# interface_temperature.net
KiCad netlist of a schematic drawn in Altium Designer
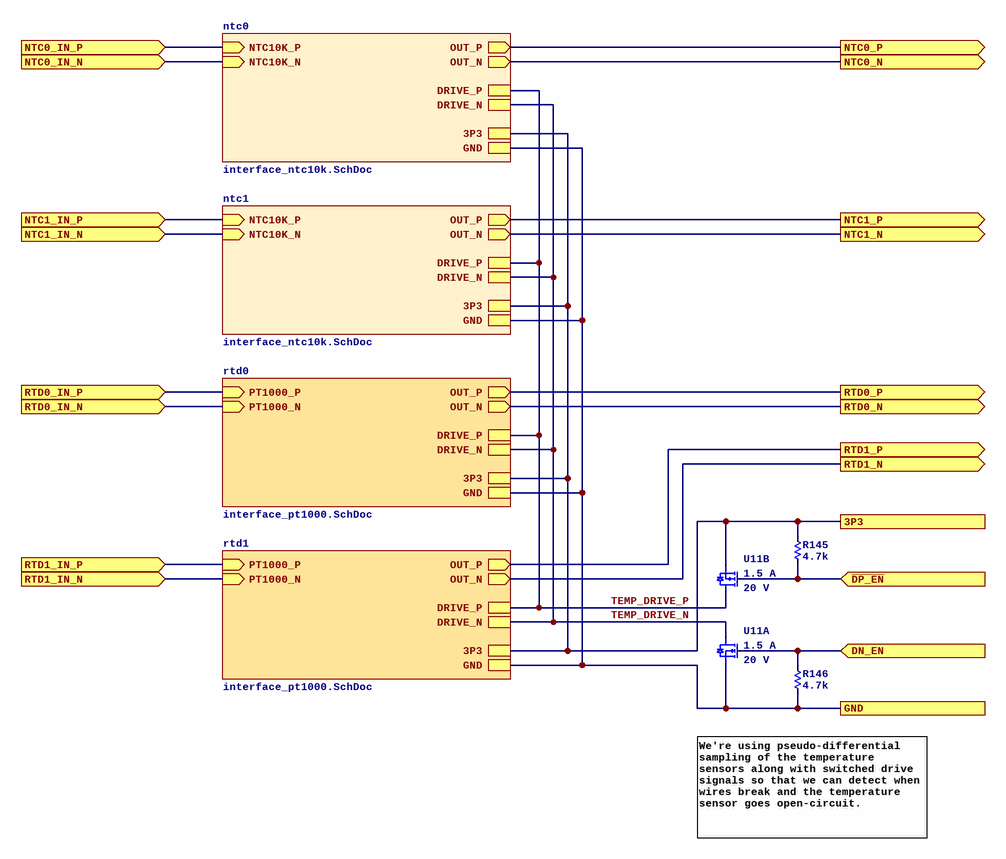
[diagram p0: interface_temperature.SchDoc]

(export (version "E")
  (design (tool "Eeschema 10.0.6"))
  (components
    (comp (ref "R145")
      (value "ERJ-2RKF4701X")
      (footprint "R0402_0.40MM")
      (description "RES SMD 4.7K OHM 1% 1/10W 0402")
      (fields
        (field (name "RESISTANCE") "4.7k")
        (field (name "TOLERANCE") "±1%")
        (field (name "MANUFACTURER") "Panasonic Electronic Components")
      )
      (libsource (lib "sscp") (part "__template_resistor"))
    )
    (comp (ref "R146")
      (value "ERJ-2RKF4701X")
      (footprint "R0402_0.40MM")
      (description "RES SMD 4.7K OHM 1% 1/10W 0402")
      (fields
        (field (name "RESISTANCE") "4.7k")
        (field (name "TOLERANCE") "±1%")
        (field (name "MANUFACTURER") "Panasonic Electronic Components")
      )
      (libsource (lib "sscp") (part "__template_resistor"))
    )
    (comp (ref "U11")
      (value "BSL215CH6327XTSA1")
      (footprint "6TSOT23")
      (description "Dual N/P-Channel 20V 140/150 mOhm 0.73/3nC OptiMOS Small Signal Mosfet - TSOP-6")
      (fields
        (field (name "MANUFACTURER") "Infineon")
        (field (name "CURRENT") "1.5 A")
        (field (name "VOLTAGE") "20 V")
      )
      (libsource (lib "SSCP") (part "NFET_PFET_20V_BSL215CH6327XTSA1"))
    )
  )
  (nets
    (net (code "1") (name "/3P3") (class "Default")
      (node (ref "R145") (pin "1") (pintype "passive"))
      (node (ref "U11") (pin "2") (pintype "passive"))
    )
    (net (code "2") (name "/DN_EN") (class "Default")
      (node (ref "R146") (pin "1") (pintype "passive"))
      (node (ref "U11") (pin "1") (pintype "passive"))
    )
    (net (code "3") (name "/GND") (class "Default")
      (node (ref "R146") (pin "2") (pintype "passive"))
      (node (ref "U11") (pin "5") (pintype "passive"))
    )
    (net (code "20") (name "/TEMP_DRIVE_N") (class "Default")
      (node (ref "U11") (pin "6") (pintype "passive"))
    )
    (net (code "21") (name "/TEMP_DRIVE_P") (class "Default")
      (node (ref "U11") (pin "4") (pintype "passive"))
    )
    (net (code "22") (name "/~{DP_EN}") (class "Default")
      (node (ref "R145") (pin "2") (pintype "passive"))
      (node (ref "U11") (pin "3") (pintype "passive"))
    )
  )
)
